# Esquema.net
KiCad netlist of a schematic drawn in EAGLE
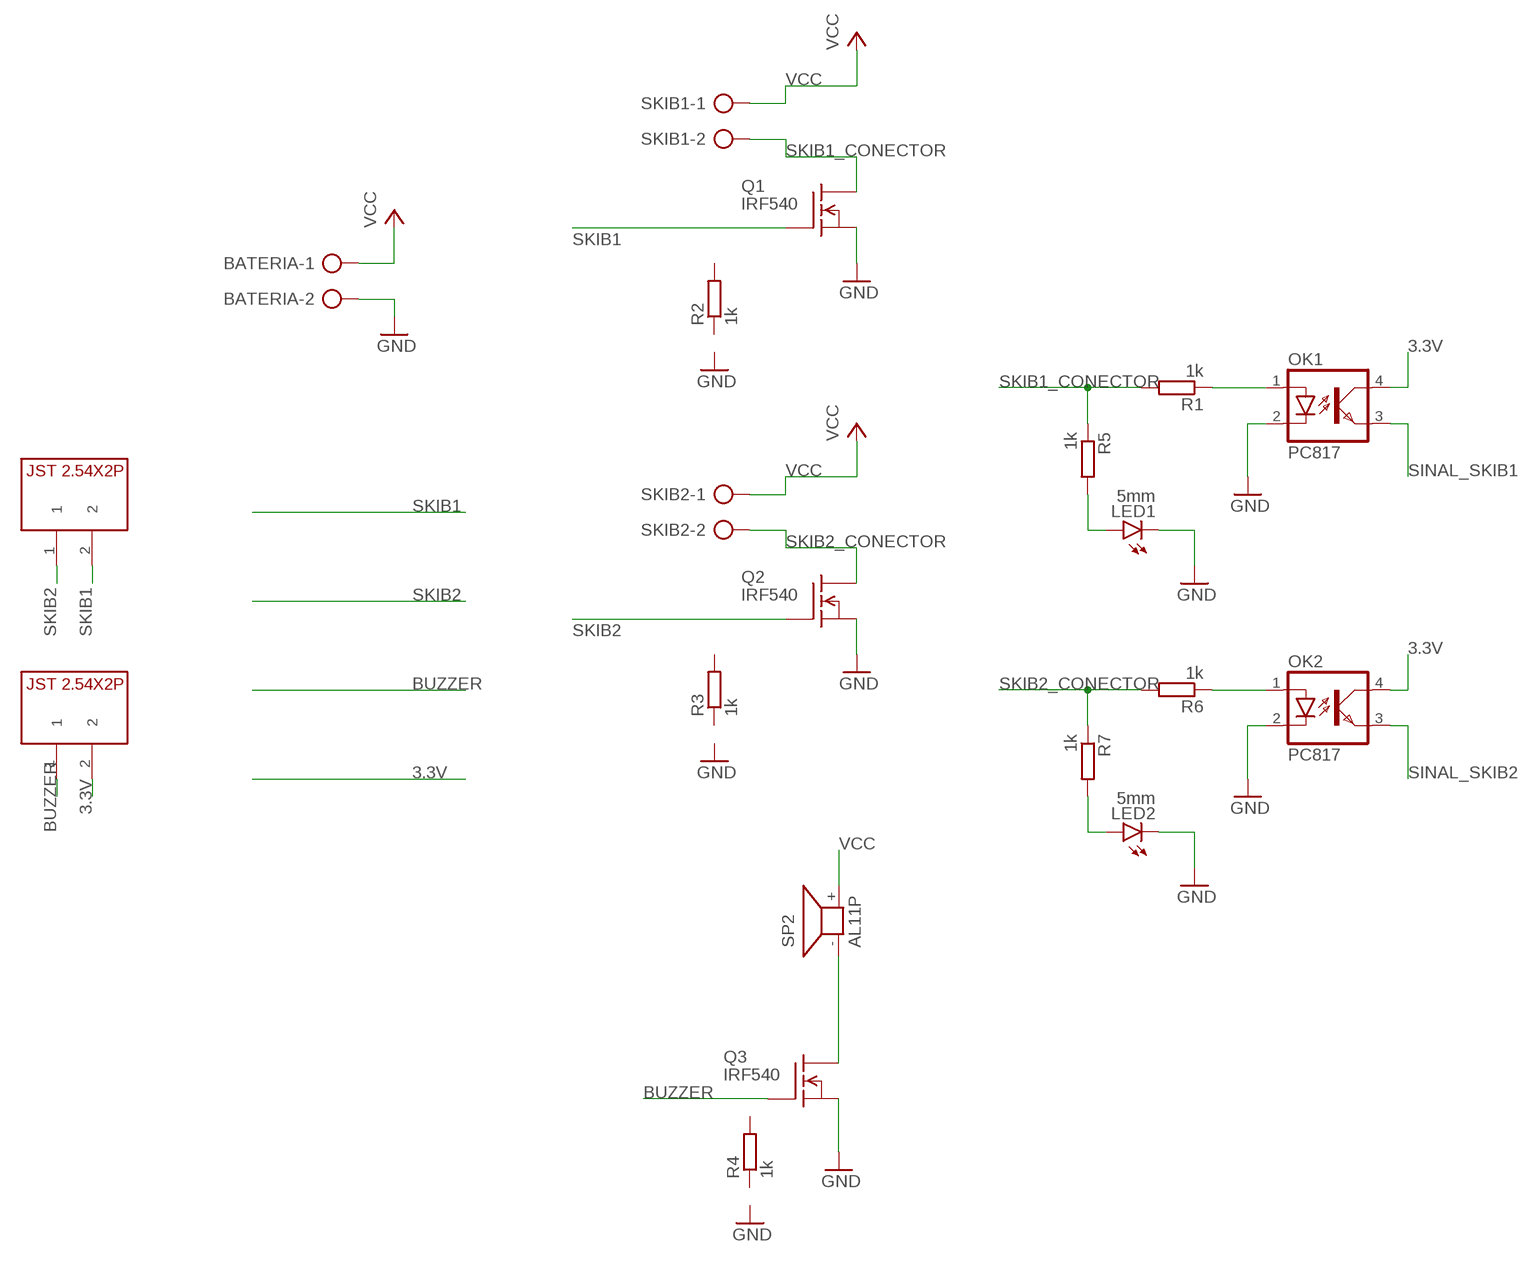
[diagram p0: schematic, sheet 1]

(export (version "E")
  (design (tool "Eeschema 10.0.6"))
  (components
    (comp (ref "BATERIA")
      (value "AK500/2-H")
      (footprint "eagle-import:AK500_2-H")
      (libsource (lib "eagle-import") (part "AK500/2-H"))
    )
    (comp (ref "LED1")
      (value "5mm")
      (footprint "eagle-import:LED5MM")
      (libsource (lib "eagle-import") (part "LED5MM"))
    )
    (comp (ref "LED2")
      (value "5mm")
      (footprint "eagle-import:LED5MM")
      (libsource (lib "eagle-import") (part "LED5MM"))
    )
    (comp (ref "OK1")
      (value "PC817")
      (footprint "eagle-import:DIL04")
      (fields (field (name "MPN") "PC817X4J000F"))
      (libsource (lib "eagle-import") (part "PC817"))
    )
    (comp (ref "OK2")
      (value "PC817")
      (footprint "eagle-import:DIL04")
      (fields (field (name "MPN") "PC817X4J000F"))
      (libsource (lib "eagle-import") (part "PC817"))
    )
    (comp (ref "Q1")
      (value "IRF540")
      (footprint "eagle-import:TO220")
      (libsource (lib "eagle-import") (part "IRF540"))
    )
    (comp (ref "Q2")
      (value "IRF540")
      (footprint "eagle-import:TO220")
      (libsource (lib "eagle-import") (part "IRF540"))
    )
    (comp (ref "Q3")
      (value "IRF540")
      (footprint "eagle-import:TO220")
      (libsource (lib "eagle-import") (part "IRF540"))
    )
    (comp (ref "R1")
      (value "1k")
      (footprint "eagle-import:0207_10")
      (libsource (lib "eagle-import") (part "R-EU_0207/10"))
    )
    (comp (ref "R2")
      (value "1k")
      (footprint "eagle-import:0207_10")
      (libsource (lib "eagle-import") (part "R-EU_0207/10"))
    )
    (comp (ref "R3")
      (value "1k")
      (footprint "eagle-import:0207_10")
      (libsource (lib "eagle-import") (part "R-EU_0207/10"))
    )
    (comp (ref "R4")
      (value "1k")
      (footprint "eagle-import:0207_10")
      (libsource (lib "eagle-import") (part "R-EU_0207/10"))
    )
    (comp (ref "R5")
      (value "1k")
      (footprint "eagle-import:0207_10")
      (libsource (lib "eagle-import") (part "R-EU_0207/10"))
    )
    (comp (ref "R6")
      (value "1k")
      (footprint "eagle-import:0207_10")
      (libsource (lib "eagle-import") (part "R-EU_0207/10"))
    )
    (comp (ref "R7")
      (value "1k")
      (footprint "eagle-import:0207_10")
      (libsource (lib "eagle-import") (part "R-EU_0207/10"))
    )
    (comp (ref "SKIB1")
      (value "AK500/2-H")
      (footprint "eagle-import:AK500_2-H")
      (libsource (lib "eagle-import") (part "AK500/2-H"))
    )
    (comp (ref "SKIB2")
      (value "AK500/2-H")
      (footprint "eagle-import:AK500_2-H")
      (libsource (lib "eagle-import") (part "AK500/2-H"))
    )
    (comp (ref "SP2")
      (value "AL11P")
      (footprint "eagle-import:AL11P")
      (libsource (lib "eagle-import") (part "AL11P"))
    )
    (comp (ref "U$1")
      (value "JST2.54X2P")
      (footprint "eagle-import:JST2.54X2P_FOOTPRINT")
      (libsource (lib "eagle-import") (part "JST2.54X2P"))
    )
    (comp (ref "U$2")
      (value "JST2.54X2P")
      (footprint "eagle-import:JST2.54X2P_FOOTPRINT")
      (libsource (lib "eagle-import") (part "JST2.54X2P"))
    )
  )
  (nets
    (net (code "1") (name "/3.3V") (class "Default")
      (node (ref "OK1") (pin "4") (pinfunction "COL_4") (pintype "passive"))
      (node (ref "OK2") (pin "4") (pinfunction "COL_4") (pintype "passive"))
      (node (ref "U$1") (pin "2") (pinfunction "2_2") (pintype "bidirectional"))
    )
    (net (code "2") (name "/BUZZER") (class "Default")
      (node (ref "Q3") (pin "1") (pinfunction "G_1") (pintype "passive"))
      (node (ref "U$1") (pin "1") (pinfunction "1_1") (pintype "bidirectional"))
    )
    (net (code "3") (name "/SINAL_SKIB1") (class "Default")
      (node (ref "OK1") (pin "3") (pinfunction "EMIT_3") (pintype "passive"))
    )
    (net (code "4") (name "/SINAL_SKIB2") (class "Default")
      (node (ref "OK2") (pin "3") (pinfunction "EMIT_3") (pintype "passive"))
    )
    (net (code "5") (name "/SKIB1") (class "Default")
      (node (ref "Q1") (pin "1") (pinfunction "G_1") (pintype "passive"))
      (node (ref "U$2") (pin "2") (pinfunction "2_2") (pintype "bidirectional"))
    )
    (net (code "6") (name "/SKIB1_CONECTOR") (class "Default")
      (node (ref "Q1") (pin "2") (pinfunction "D_2") (pintype "passive"))
      (node (ref "R1") (pin "2") (pinfunction "2_2") (pintype "passive"))
      (node (ref "R5") (pin "1") (pinfunction "1_1") (pintype "passive"))
      (node (ref "SKIB1") (pin "2") (pinfunction "KL_2") (pintype "passive"))
    )
    (net (code "7") (name "/SKIB2") (class "Default")
      (node (ref "Q2") (pin "1") (pinfunction "G_1") (pintype "passive"))
      (node (ref "U$2") (pin "1") (pinfunction "1_1") (pintype "bidirectional"))
    )
    (net (code "8") (name "/SKIB2_CONECTOR") (class "Default")
      (node (ref "Q2") (pin "2") (pinfunction "D_2") (pintype "passive"))
      (node (ref "R6") (pin "2") (pinfunction "2_2") (pintype "passive"))
      (node (ref "R7") (pin "1") (pinfunction "1_1") (pintype "passive"))
      (node (ref "SKIB2") (pin "2") (pinfunction "KL_2") (pintype "passive"))
    )
    (net (code "9") (name "GND") (class "Default")
      (node (ref "BATERIA") (pin "2") (pinfunction "KL_2") (pintype "passive"))
      (node (ref "LED1") (pin "K") (pinfunction "C_K") (pintype "passive"))
      (node (ref "LED2") (pin "K") (pinfunction "C_K") (pintype "passive"))
      (node (ref "OK1") (pin "2") (pinfunction "C_2") (pintype "passive"))
      (node (ref "OK2") (pin "2") (pinfunction "C_2") (pintype "passive"))
      (node (ref "Q1") (pin "3") (pinfunction "S_3") (pintype "passive"))
      (node (ref "Q2") (pin "3") (pinfunction "S_3") (pintype "passive"))
      (node (ref "Q3") (pin "3") (pinfunction "S_3") (pintype "passive"))
    )
    (net (code "10") (name "Net-(LED1-PadA)") (class "Default")
      (node (ref "LED1") (pin "A") (pinfunction "A_A") (pintype "passive"))
      (node (ref "R5") (pin "2") (pinfunction "2_2") (pintype "passive"))
    )
    (net (code "11") (name "Net-(LED2-PadA)") (class "Default")
      (node (ref "LED2") (pin "A") (pinfunction "A_A") (pintype "passive"))
      (node (ref "R7") (pin "2") (pinfunction "2_2") (pintype "passive"))
    )
    (net (code "12") (name "Net-(OK1-A)") (class "Default")
      (node (ref "OK1") (pin "1") (pinfunction "A_1") (pintype "passive"))
      (node (ref "R1") (pin "1") (pinfunction "1_1") (pintype "passive"))
    )
    (net (code "13") (name "Net-(OK2-A)") (class "Default")
      (node (ref "OK2") (pin "1") (pinfunction "A_1") (pintype "passive"))
      (node (ref "R6") (pin "1") (pinfunction "1_1") (pintype "passive"))
    )
    (net (code "14") (name "Net-(Q3-D)") (class "Default")
      (node (ref "Q3") (pin "2") (pinfunction "D_2") (pintype "passive"))
      (node (ref "SP2") (pin "-") (pinfunction "1_-") (pintype "passive"))
    )
    (net (code "15") (name "VCC") (class "Default")
      (node (ref "BATERIA") (pin "1") (pinfunction "KL_1") (pintype "passive"))
      (node (ref "SKIB1") (pin "1") (pinfunction "KL_1") (pintype "passive"))
      (node (ref "SKIB2") (pin "1") (pinfunction "KL_1") (pintype "passive"))
      (node (ref "SP2") (pin "+") (pinfunction "2_+") (pintype "passive"))
    )
    (net (code "16") (name "unconnected-(R2-Pad1)") (class "Default")
      (node (ref "R2") (pin "1") (pinfunction "1_1") (pintype "passive"))
    )
    (net (code "17") (name "unconnected-(R2-Pad2)") (class "Default")
      (node (ref "R2") (pin "2") (pinfunction "2_2") (pintype "passive"))
    )
    (net (code "18") (name "unconnected-(R3-Pad1)") (class "Default")
      (node (ref "R3") (pin "1") (pinfunction "1_1") (pintype "passive"))
    )
    (net (code "19") (name "unconnected-(R3-Pad2)") (class "Default")
      (node (ref "R3") (pin "2") (pinfunction "2_2") (pintype "passive"))
    )
    (net (code "20") (name "unconnected-(R4-Pad1)") (class "Default")
      (node (ref "R4") (pin "1") (pinfunction "1_1") (pintype "passive"))
    )
    (net (code "21") (name "unconnected-(R4-Pad2)") (class "Default")
      (node (ref "R4") (pin "2") (pinfunction "2_2") (pintype "passive"))
    )
  )
)
